# fridge_module.net
KiCad netlist of a schematic drawn in Altium Designer
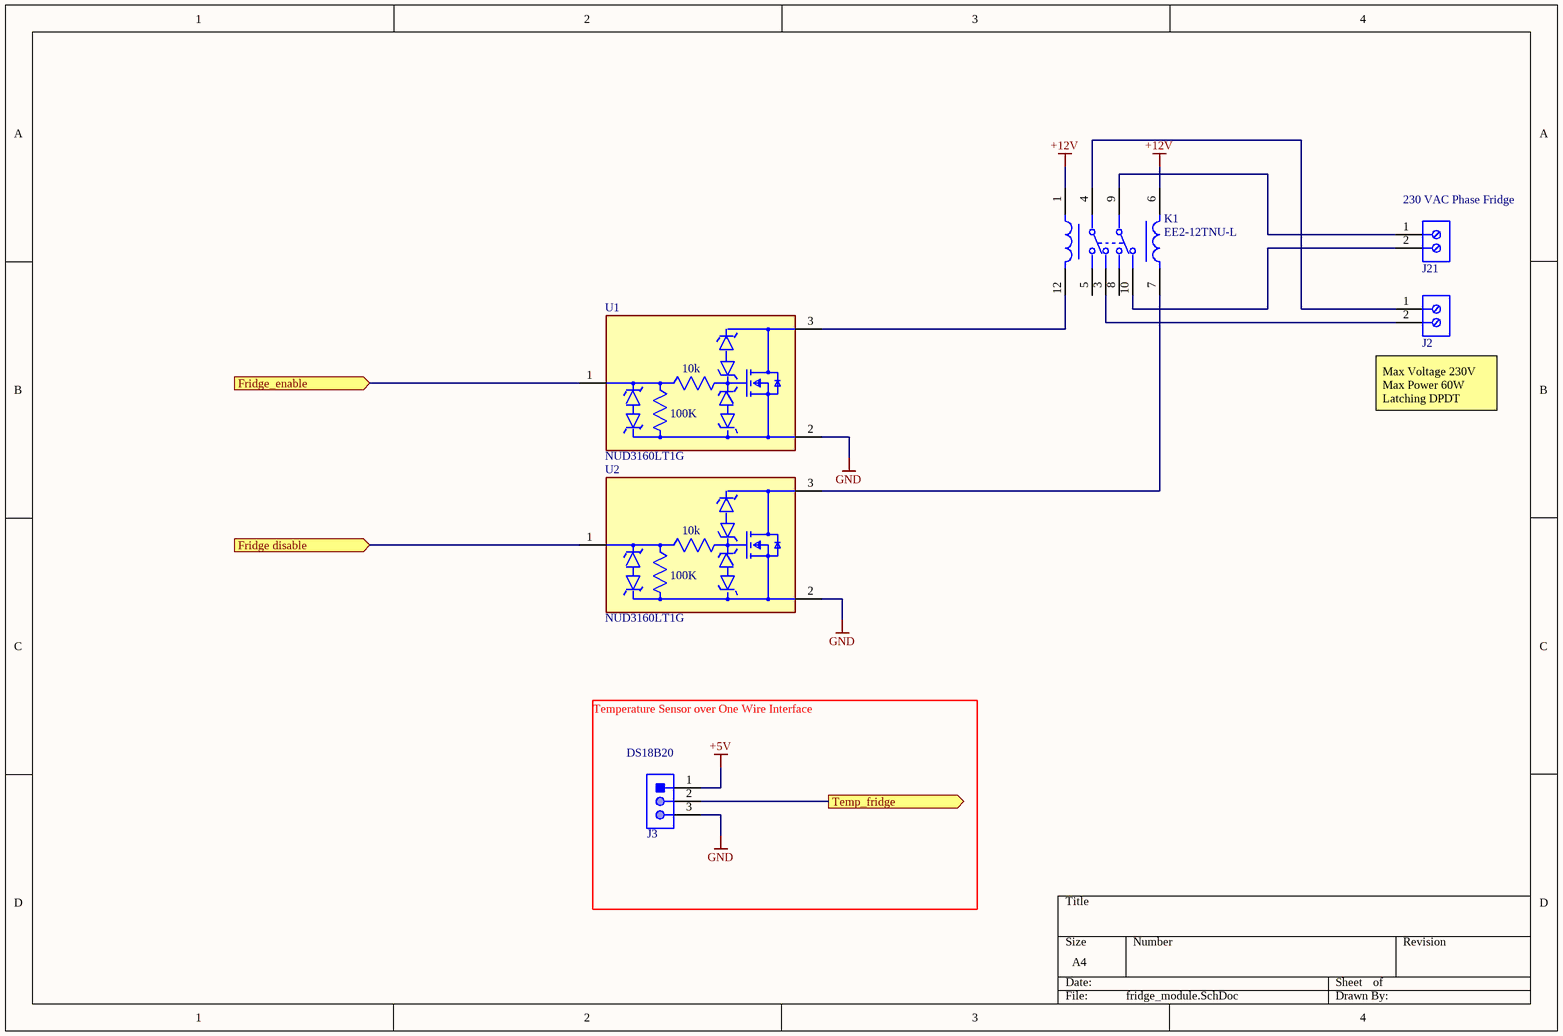
[diagram p0: fridge_module.SchDoc]

(export (version "E")
  (design (tool "Eeschema 10.0.6"))
  (components
    (comp (ref "J2")
      (value "282836-2")
      (footprint "TECO-282836-2_V")
      (description "Female Header, Pitch 5 mm, 1 x 2 Position, Height 10 mm, Tail Length 3.5 mm, Rohs, Bulk")
      (fields (field (name "VOLTAGE") "300V") (field (name "MANUFACTURER") "TE Connectivity"))
      (libsource (lib "Altium Content Vault") (part "CN-1P-F-TB2"))
    )
    (comp (ref "J3")
      (value "JST-S3B-PH-SM4-TB-3_V")
      (footprint "JST-S3B-PH-SM4-TB-3_V")
      (libsource (lib "integrated_library") (part "CONNECTOR_JST-S3B-PH-SM4"))
    )
    (comp (ref "J21")
      (value "282836-2")
      (footprint "TECO-282836-2_V")
      (description "Female Header, Pitch 5 mm, 1 x 2 Position, Height 10 mm, Tail Length 3.5 mm, Rohs, Bulk")
      (fields (field (name "VOLTAGE") "300V") (field (name "MANUFACTURER") "TE Connectivity"))
      (libsource (lib "Altium Content Vault") (part "CN-1P-F-TB2"))
    )
    (comp (ref "K1")
      (value "EE2-12TNU-L")
      (footprint "FP-EE2-12TNU-L-MFG")
      (description "RELAY GEN PURPOSE DPDT 2A 12VDC")
      (libsource (lib "Altium Content Vault") (part "a2c4c419374dacc8730513353986d3a"))
    )
    (comp (ref "U1")
      (value "NUD3160LT1G")
      (footprint "FP-318-08-MFG")
      (description "IC INDCT LOAD DRVR INDUST SOT23")
      (fields
        (field (name "OCTOPART") "https://octopart.com/nud3160lt1g-on+semiconductor-470723")
        (field (name "MANUFACTURER") "ON Semiconductor")
      )
      (libsource (lib "Altium Content Vault") (part "3565ae214b0a124fee97343a38643ca"))
    )
    (comp (ref "U2")
      (value "NUD3160LT1G")
      (footprint "FP-318-08-MFG")
      (description "IC INDCT LOAD DRVR INDUST SOT23")
      (fields
        (field (name "OCTOPART") "https://octopart.com/nud3160lt1g-on+semiconductor-470723")
        (field (name "MANUFACTURER") "ON Semiconductor")
      )
      (libsource (lib "Altium Content Vault") (part "3565ae214b0a124fee97343a38643ca"))
    )
  )
  (nets
    (net (code "1") (name "+5V") (class "Default")
      (node (ref "J3") (pin "1") (pinfunction "1_1") (pintype "passive"))
    )
    (net (code "2") (name "+12V") (class "Default")
      (node (ref "K1") (pin "1") (pinfunction "SET+_1") (pintype "passive"))
      (node (ref "K1") (pin "6") (pinfunction "RESET+_6") (pintype "passive"))
    )
    (net (code "3") (name "/Fridge disable") (class "Default")
      (node (ref "U2") (pin "1") (pinfunction "Gate_1") (pintype "passive"))
    )
    (net (code "4") (name "/Fridge_enable") (class "Default")
      (node (ref "U1") (pin "1") (pinfunction "Gate_1") (pintype "passive"))
    )
    (net (code "5") (name "/Temp_fridge") (class "Default")
      (node (ref "J3") (pin "2") (pinfunction "2_2") (pintype "passive"))
    )
    (net (code "6") (name "GND") (class "Default")
      (node (ref "J3") (pin "3") (pinfunction "3_3") (pintype "passive"))
      (node (ref "U1") (pin "2") (pinfunction "Source_2") (pintype "passive"))
      (node (ref "U2") (pin "2") (pinfunction "Source_2") (pintype "passive"))
    )
    (net (code "7") (name "Net-(J2-Pad1)") (class "Default")
      (node (ref "J2") (pin "1") (pinfunction "1_1") (pintype "passive"))
      (node (ref "K1") (pin "4") (pinfunction "4_4") (pintype "passive"))
    )
    (net (code "8") (name "Net-(J2-Pad2)") (class "Default")
      (node (ref "J2") (pin "2") (pinfunction "2_2") (pintype "passive"))
      (node (ref "K1") (pin "3") (pinfunction "3_3") (pintype "passive"))
    )
    (net (code "9") (name "Net-(J21-Pad1)") (class "Default")
      (node (ref "J21") (pin "1") (pinfunction "1_1") (pintype "passive"))
      (node (ref "K1") (pin "9") (pinfunction "9_9") (pintype "passive"))
    )
    (net (code "10") (name "Net-(J21-Pad2)") (class "Default")
      (node (ref "J21") (pin "2") (pinfunction "2_2") (pintype "passive"))
      (node (ref "K1") (pin "10") (pinfunction "10_10") (pintype "passive"))
    )
    (net (code "11") (name "Net-(K1-RESET-)") (class "Default")
      (node (ref "K1") (pin "7") (pinfunction "RESET-_7") (pintype "passive"))
      (node (ref "U2") (pin "3") (pinfunction "Drain_3") (pintype "passive"))
    )
    (net (code "12") (name "Net-(K1-SET-)") (class "Default")
      (node (ref "K1") (pin "12") (pinfunction "SET-_12") (pintype "passive"))
      (node (ref "U1") (pin "3") (pinfunction "Drain_3") (pintype "passive"))
    )
    (net (code "13") (name "unconnected-(K1-Pad5)") (class "Default")
      (node (ref "K1") (pin "5") (pinfunction "5_5") (pintype "passive"))
    )
    (net (code "14") (name "unconnected-(K1-Pad8)") (class "Default")
      (node (ref "K1") (pin "8") (pinfunction "8_8") (pintype "passive"))
    )
  )
)
